# RTC.net
KiCad netlist of a schematic drawn in EAGLE
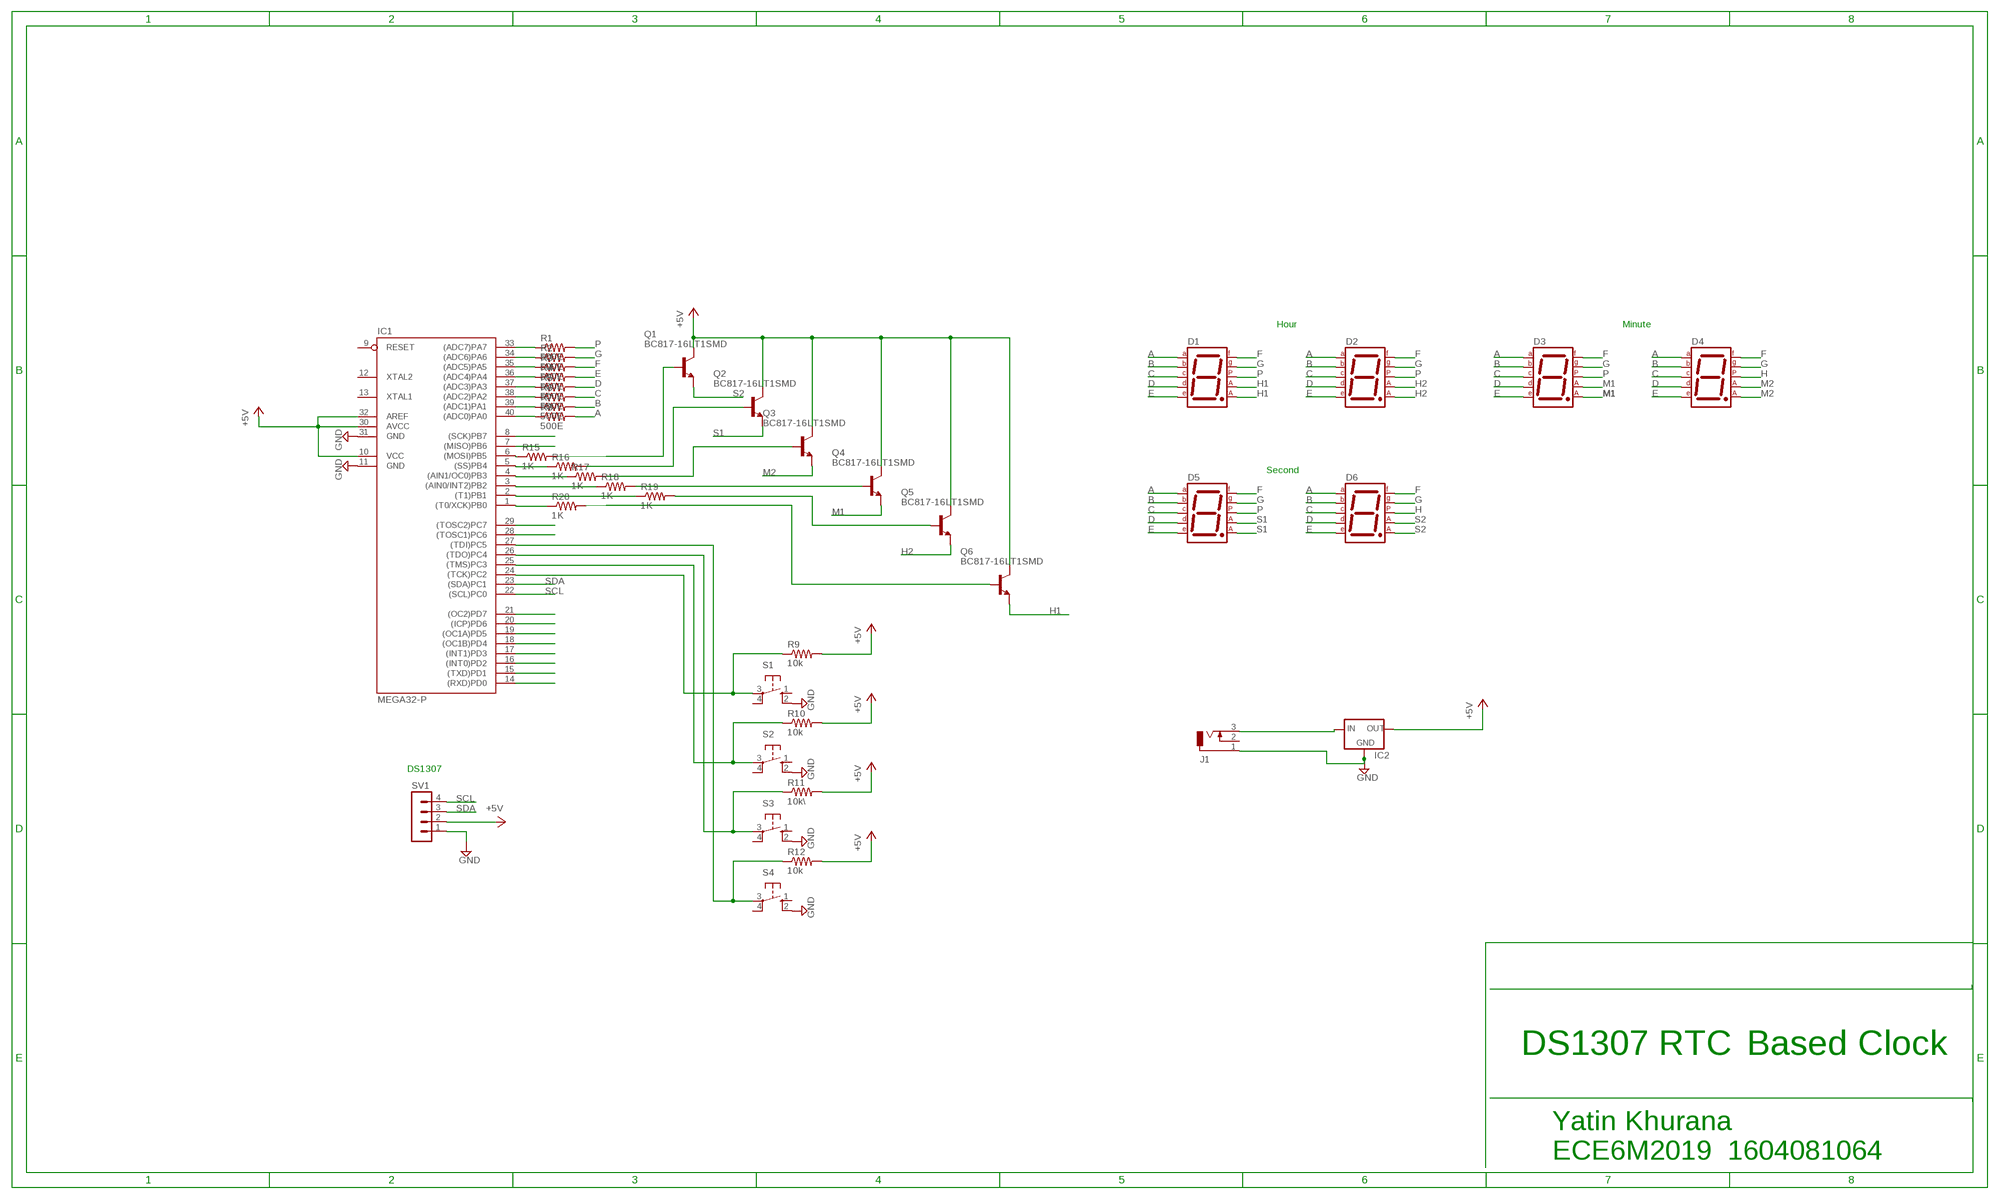
[diagram p0: schematic, sheet 1]

(export (version "E")
  (design (tool "Eeschema 10.0.6"))
  (components
    (comp (ref "D1")
      (value "7SEG-CA")
      (footprint "eagle-import:7SEG-13")
      (libsource (lib "eagle-import") (part "7SEG-CA"))
    )
    (comp (ref "D2")
      (value "7SEG-CA")
      (footprint "eagle-import:7SEG-13")
      (libsource (lib "eagle-import") (part "7SEG-CA"))
    )
    (comp (ref "D3")
      (value "7SEG-CA")
      (footprint "eagle-import:7SEG-13")
      (libsource (lib "eagle-import") (part "7SEG-CA"))
    )
    (comp (ref "D4")
      (value "7SEG-CA")
      (footprint "eagle-import:7SEG-13")
      (libsource (lib "eagle-import") (part "7SEG-CA"))
    )
    (comp (ref "D5")
      (value "7SEG-CA")
      (footprint "eagle-import:7SEG-13")
      (libsource (lib "eagle-import") (part "7SEG-CA"))
    )
    (comp (ref "D6")
      (value "7SEG-CA")
      (footprint "eagle-import:7SEG-13")
      (libsource (lib "eagle-import") (part "7SEG-CA"))
    )
    (comp (ref "IC1")
      (value "MEGA32-P")
      (footprint "eagle-import:DIL40")
      (fields (field (name "MPN") "ATMEGA32-16PU"))
      (libsource (lib "eagle-import") (part "MEGA32-P"))
    )
    (comp (ref "IC2")
      (value "78XXS")
      (footprint "eagle-import:78XXS")
      (libsource (lib "eagle-import") (part "78XXS"))
    )
    (comp (ref "J1")
      (value "DCJ0303")
      (footprint "eagle-import:DCJ0303")
      (libsource (lib "eagle-import") (part "DCJ0303"))
    )
    (comp (ref "Q1")
      (value "BC817-16LT1SMD")
      (footprint "eagle-import:SOT23-BEC")
      (libsource (lib "eagle-import") (part "BC817SMD-16LT1"))
    )
    (comp (ref "Q2")
      (value "BC817-16LT1SMD")
      (footprint "eagle-import:SOT23-BEC")
      (libsource (lib "eagle-import") (part "BC817SMD-16LT1"))
    )
    (comp (ref "Q3")
      (value "BC817-16LT1SMD")
      (footprint "eagle-import:SOT23-BEC")
      (libsource (lib "eagle-import") (part "BC817SMD-16LT1"))
    )
    (comp (ref "Q4")
      (value "BC817-16LT1SMD")
      (footprint "eagle-import:SOT23-BEC")
      (libsource (lib "eagle-import") (part "BC817SMD-16LT1"))
    )
    (comp (ref "Q5")
      (value "BC817-16LT1SMD")
      (footprint "eagle-import:SOT23-BEC")
      (libsource (lib "eagle-import") (part "BC817SMD-16LT1"))
    )
    (comp (ref "Q6")
      (value "BC817-16LT1SMD")
      (footprint "eagle-import:SOT23-BEC")
      (libsource (lib "eagle-import") (part "BC817SMD-16LT1"))
    )
    (comp (ref "R1")
      (value "500E")
      (footprint "eagle-import:M1206")
      (libsource (lib "eagle-import") (part "R-US_M1206"))
    )
    (comp (ref "R2")
      (value "500E")
      (footprint "eagle-import:M1206")
      (libsource (lib "eagle-import") (part "R-US_M1206"))
    )
    (comp (ref "R3")
      (value "500E")
      (footprint "eagle-import:M1206")
      (libsource (lib "eagle-import") (part "R-US_M1206"))
    )
    (comp (ref "R4")
      (value "500E")
      (footprint "eagle-import:M1206")
      (libsource (lib "eagle-import") (part "R-US_M1206"))
    )
    (comp (ref "R5")
      (value "500E")
      (footprint "eagle-import:M1206")
      (libsource (lib "eagle-import") (part "R-US_M1206"))
    )
    (comp (ref "R6")
      (value "500E")
      (footprint "eagle-import:M1206")
      (libsource (lib "eagle-import") (part "R-US_M1206"))
    )
    (comp (ref "R7")
      (value "500E")
      (footprint "eagle-import:M1206")
      (libsource (lib "eagle-import") (part "R-US_M1206"))
    )
    (comp (ref "R8")
      (value "500E")
      (footprint "eagle-import:M1206")
      (libsource (lib "eagle-import") (part "R-US_M1206"))
    )
    (comp (ref "R9")
      (value "10k")
      (footprint "eagle-import:M1206")
      (libsource (lib "eagle-import") (part "R-US_M1206"))
    )
    (comp (ref "R10")
      (value "10k")
      (footprint "eagle-import:M1206")
      (libsource (lib "eagle-import") (part "R-US_M1206"))
    )
    (comp (ref "R11")
      (value "10k\\")
      (footprint "eagle-import:M1206")
      (libsource (lib "eagle-import") (part "R-US_M1206"))
    )
    (comp (ref "R12")
      (value "10k")
      (footprint "eagle-import:M1206")
      (libsource (lib "eagle-import") (part "R-US_M1206"))
    )
    (comp (ref "R15")
      (value "1K")
      (footprint "eagle-import:M1206")
      (libsource (lib "eagle-import") (part "R-US_M1206"))
    )
    (comp (ref "R16")
      (value "1K")
      (footprint "eagle-import:M1206")
      (libsource (lib "eagle-import") (part "R-US_M1206"))
    )
    (comp (ref "R17")
      (value "1K")
      (footprint "eagle-import:M1206")
      (libsource (lib "eagle-import") (part "R-US_M1206"))
    )
    (comp (ref "R18")
      (value "1K")
      (footprint "eagle-import:M1206")
      (libsource (lib "eagle-import") (part "R-US_M1206"))
    )
    (comp (ref "R19")
      (value "1K")
      (footprint "eagle-import:M1206")
      (libsource (lib "eagle-import") (part "R-US_M1206"))
    )
    (comp (ref "R20")
      (value "1K")
      (footprint "eagle-import:M1206")
      (libsource (lib "eagle-import") (part "R-US_M1206"))
    )
    (comp (ref "S1")
      (value "10-XX")
      (footprint "eagle-import:B3F-10XX")
      (fields (field (name "MPN") "B3F-1000"))
      (libsource (lib "eagle-import") (part "10-XX"))
    )
    (comp (ref "S2")
      (value "10-XX")
      (footprint "eagle-import:B3F-10XX")
      (fields (field (name "MPN") "B3F-1000"))
      (libsource (lib "eagle-import") (part "10-XX"))
    )
    (comp (ref "S3")
      (value "10-XX")
      (footprint "eagle-import:B3F-10XX")
      (fields (field (name "MPN") "B3F-1000"))
      (libsource (lib "eagle-import") (part "10-XX"))
    )
    (comp (ref "S4")
      (value "10-XX")
      (footprint "eagle-import:B3F-10XX")
      (fields (field (name "MPN") "B3F-1000"))
      (libsource (lib "eagle-import") (part "10-XX"))
    )
    (comp (ref "SV1")
      (value "MA04-1")
      (footprint "eagle-import:MA04-1")
      (libsource (lib "eagle-import") (part "MA04-1"))
    )
  )
  (nets
    (net (code "1") (name "+5V") (class "Default")
      (node (ref "IC1") (pin "10") (pinfunction "VCC_10") (pintype "power_in"))
      (node (ref "IC1") (pin "30") (pinfunction "AVCC_30") (pintype "power_in"))
      (node (ref "IC1") (pin "32") (pinfunction "AREF_32") (pintype "passive"))
      (node (ref "IC2") (pin "OUT") (pinfunction "OUT_OUT") (pintype "passive"))
      (node (ref "Q1") (pin "C") (pinfunction "C_C") (pintype "passive"))
      (node (ref "Q2") (pin "C") (pinfunction "C_C") (pintype "passive"))
      (node (ref "Q3") (pin "C") (pinfunction "C_C") (pintype "passive"))
      (node (ref "Q4") (pin "C") (pinfunction "C_C") (pintype "passive"))
      (node (ref "Q5") (pin "C") (pinfunction "C_C") (pintype "passive"))
      (node (ref "Q6") (pin "C") (pinfunction "C_C") (pintype "passive"))
      (node (ref "R10") (pin "2") (pinfunction "2_2") (pintype "passive"))
      (node (ref "R11") (pin "2") (pinfunction "2_2") (pintype "passive"))
      (node (ref "R12") (pin "2") (pinfunction "2_2") (pintype "passive"))
      (node (ref "R9") (pin "2") (pinfunction "2_2") (pintype "passive"))
      (node (ref "SV1") (pin "2") (pinfunction "2_2") (pintype "passive"))
    )
    (net (code "2") (name "/A") (class "Default")
      (node (ref "D1") (pin "7") (pinfunction "A_7") (pintype "passive"))
      (node (ref "D2") (pin "7") (pinfunction "A_7") (pintype "passive"))
      (node (ref "D3") (pin "7") (pinfunction "A_7") (pintype "passive"))
      (node (ref "D4") (pin "7") (pinfunction "A_7") (pintype "passive"))
      (node (ref "D5") (pin "7") (pinfunction "A_7") (pintype "passive"))
      (node (ref "D6") (pin "7") (pinfunction "A_7") (pintype "passive"))
      (node (ref "R8") (pin "2") (pinfunction "2_2") (pintype "passive"))
    )
    (net (code "3") (name "/B") (class "Default")
      (node (ref "D1") (pin "6") (pinfunction "B_6") (pintype "passive"))
      (node (ref "D2") (pin "6") (pinfunction "B_6") (pintype "passive"))
      (node (ref "D3") (pin "6") (pinfunction "B_6") (pintype "passive"))
      (node (ref "D4") (pin "6") (pinfunction "B_6") (pintype "passive"))
      (node (ref "D5") (pin "6") (pinfunction "B_6") (pintype "passive"))
      (node (ref "D6") (pin "6") (pinfunction "B_6") (pintype "passive"))
      (node (ref "R7") (pin "2") (pinfunction "2_2") (pintype "passive"))
    )
    (net (code "4") (name "/C") (class "Default")
      (node (ref "D1") (pin "4") (pinfunction "C_4") (pintype "passive"))
      (node (ref "D2") (pin "4") (pinfunction "C_4") (pintype "passive"))
      (node (ref "D3") (pin "4") (pinfunction "C_4") (pintype "passive"))
      (node (ref "D4") (pin "4") (pinfunction "C_4") (pintype "passive"))
      (node (ref "D5") (pin "4") (pinfunction "C_4") (pintype "passive"))
      (node (ref "D6") (pin "4") (pinfunction "C_4") (pintype "passive"))
      (node (ref "R6") (pin "2") (pinfunction "2_2") (pintype "passive"))
    )
    (net (code "5") (name "/D") (class "Default")
      (node (ref "D1") (pin "2") (pinfunction "D_2") (pintype "passive"))
      (node (ref "D2") (pin "2") (pinfunction "D_2") (pintype "passive"))
      (node (ref "D3") (pin "2") (pinfunction "D_2") (pintype "passive"))
      (node (ref "D4") (pin "2") (pinfunction "D_2") (pintype "passive"))
      (node (ref "D5") (pin "2") (pinfunction "D_2") (pintype "passive"))
      (node (ref "D6") (pin "2") (pinfunction "D_2") (pintype "passive"))
      (node (ref "R5") (pin "2") (pinfunction "2_2") (pintype "passive"))
    )
    (net (code "6") (name "/E") (class "Default")
      (node (ref "D1") (pin "1") (pinfunction "E_1") (pintype "passive"))
      (node (ref "D2") (pin "1") (pinfunction "E_1") (pintype "passive"))
      (node (ref "D3") (pin "1") (pinfunction "E_1") (pintype "passive"))
      (node (ref "D4") (pin "1") (pinfunction "E_1") (pintype "passive"))
      (node (ref "D5") (pin "1") (pinfunction "E_1") (pintype "passive"))
      (node (ref "D6") (pin "1") (pinfunction "E_1") (pintype "passive"))
      (node (ref "R4") (pin "2") (pinfunction "2_2") (pintype "passive"))
    )
    (net (code "7") (name "/F") (class "Default")
      (node (ref "D1") (pin "9") (pinfunction "F_9") (pintype "passive"))
      (node (ref "D2") (pin "9") (pinfunction "F_9") (pintype "passive"))
      (node (ref "D3") (pin "9") (pinfunction "F_9") (pintype "passive"))
      (node (ref "D4") (pin "9") (pinfunction "F_9") (pintype "passive"))
      (node (ref "D5") (pin "9") (pinfunction "F_9") (pintype "passive"))
      (node (ref "D6") (pin "9") (pinfunction "F_9") (pintype "passive"))
      (node (ref "R3") (pin "2") (pinfunction "2_2") (pintype "passive"))
    )
    (net (code "8") (name "/G") (class "Default")
      (node (ref "D1") (pin "10") (pinfunction "G_10") (pintype "passive"))
      (node (ref "D2") (pin "10") (pinfunction "G_10") (pintype "passive"))
      (node (ref "D3") (pin "10") (pinfunction "G_10") (pintype "passive"))
      (node (ref "D4") (pin "10") (pinfunction "G_10") (pintype "passive"))
      (node (ref "D5") (pin "10") (pinfunction "G_10") (pintype "passive"))
      (node (ref "D6") (pin "10") (pinfunction "G_10") (pintype "passive"))
      (node (ref "R2") (pin "2") (pinfunction "2_2") (pintype "passive"))
    )
    (net (code "9") (name "/H") (class "Default")
      (node (ref "D4") (pin "5") (pinfunction "DP_5") (pintype "passive"))
      (node (ref "D6") (pin "5") (pinfunction "DP_5") (pintype "passive"))
    )
    (net (code "10") (name "/H1") (class "Default")
      (node (ref "D1") (pin "3") (pinfunction "CA1_3") (pintype "passive"))
      (node (ref "D1") (pin "8") (pinfunction "CA2_8") (pintype "passive"))
      (node (ref "Q6") (pin "E") (pinfunction "E_E") (pintype "passive"))
    )
    (net (code "11") (name "/H2") (class "Default")
      (node (ref "D2") (pin "3") (pinfunction "CA1_3") (pintype "passive"))
      (node (ref "D2") (pin "8") (pinfunction "CA2_8") (pintype "passive"))
      (node (ref "Q5") (pin "E") (pinfunction "E_E") (pintype "passive"))
    )
    (net (code "12") (name "/M1") (class "Default")
      (node (ref "D3") (pin "3") (pinfunction "CA1_3") (pintype "passive"))
      (node (ref "D3") (pin "8") (pinfunction "CA2_8") (pintype "passive"))
      (node (ref "Q4") (pin "E") (pinfunction "E_E") (pintype "passive"))
    )
    (net (code "13") (name "/M2") (class "Default")
      (node (ref "D4") (pin "3") (pinfunction "CA1_3") (pintype "passive"))
      (node (ref "D4") (pin "8") (pinfunction "CA2_8") (pintype "passive"))
      (node (ref "Q3") (pin "E") (pinfunction "E_E") (pintype "passive"))
    )
    (net (code "14") (name "/P") (class "Default")
      (node (ref "D1") (pin "5") (pinfunction "DP_5") (pintype "passive"))
      (node (ref "D2") (pin "5") (pinfunction "DP_5") (pintype "passive"))
      (node (ref "D3") (pin "5") (pinfunction "DP_5") (pintype "passive"))
      (node (ref "D5") (pin "5") (pinfunction "DP_5") (pintype "passive"))
      (node (ref "R1") (pin "2") (pinfunction "2_2") (pintype "passive"))
    )
    (net (code "15") (name "/S1") (class "Default")
      (node (ref "D5") (pin "3") (pinfunction "CA1_3") (pintype "passive"))
      (node (ref "D5") (pin "8") (pinfunction "CA2_8") (pintype "passive"))
      (node (ref "Q2") (pin "E") (pinfunction "E_E") (pintype "passive"))
    )
    (net (code "16") (name "/S2") (class "Default")
      (node (ref "D6") (pin "3") (pinfunction "CA1_3") (pintype "passive"))
      (node (ref "D6") (pin "8") (pinfunction "CA2_8") (pintype "passive"))
      (node (ref "Q1") (pin "E") (pinfunction "E_E") (pintype "passive"))
    )
    (net (code "17") (name "/SCL") (class "Default")
      (node (ref "IC1") (pin "22") (pinfunction "(SCL)PC0_22") (pintype "bidirectional"))
      (node (ref "SV1") (pin "4") (pinfunction "4_4") (pintype "passive"))
    )
    (net (code "18") (name "/SDA") (class "Default")
      (node (ref "IC1") (pin "23") (pinfunction "(SDA)PC1_23") (pintype "bidirectional"))
      (node (ref "SV1") (pin "3") (pinfunction "3_3") (pintype "passive"))
    )
    (net (code "19") (name "GND") (class "Default")
      (node (ref "IC1") (pin "11") (pinfunction "GND_11") (pintype "power_in"))
      (node (ref "IC1") (pin "31") (pinfunction "GND_31") (pintype "power_in"))
      (node (ref "IC2") (pin "GND") (pinfunction "GND_GND") (pintype "input"))
      (node (ref "J1") (pin "1") (pinfunction "1_1") (pintype "passive"))
      (node (ref "S1") (pin "2") (pinfunction "S1_2") (pintype "passive"))
      (node (ref "S2") (pin "2") (pinfunction "S1_2") (pintype "passive"))
      (node (ref "S3") (pin "2") (pinfunction "S1_2") (pintype "passive"))
      (node (ref "S4") (pin "2") (pinfunction "S1_2") (pintype "passive"))
      (node (ref "SV1") (pin "1") (pinfunction "1_1") (pintype "passive"))
    )
    (net (code "20") (name "Net-(IC1-(ADC0)PA0)") (class "Default")
      (node (ref "IC1") (pin "40") (pinfunction "(ADC0)PA0_40") (pintype "bidirectional"))
      (node (ref "R8") (pin "1") (pinfunction "1_1") (pintype "passive"))
    )
    (net (code "21") (name "Net-(IC1-(ADC1)PA1)") (class "Default")
      (node (ref "IC1") (pin "39") (pinfunction "(ADC1)PA1_39") (pintype "bidirectional"))
      (node (ref "R7") (pin "1") (pinfunction "1_1") (pintype "passive"))
    )
    (net (code "22") (name "Net-(IC1-(ADC2)PA2)") (class "Default")
      (node (ref "IC1") (pin "38") (pinfunction "(ADC2)PA2_38") (pintype "bidirectional"))
      (node (ref "R6") (pin "1") (pinfunction "1_1") (pintype "passive"))
    )
    (net (code "23") (name "Net-(IC1-(ADC3)PA3)") (class "Default")
      (node (ref "IC1") (pin "37") (pinfunction "(ADC3)PA3_37") (pintype "bidirectional"))
      (node (ref "R5") (pin "1") (pinfunction "1_1") (pintype "passive"))
    )
    (net (code "24") (name "Net-(IC1-(ADC4)PA4)") (class "Default")
      (node (ref "IC1") (pin "36") (pinfunction "(ADC4)PA4_36") (pintype "bidirectional"))
      (node (ref "R4") (pin "1") (pinfunction "1_1") (pintype "passive"))
    )
    (net (code "25") (name "Net-(IC1-(ADC5)PA5)") (class "Default")
      (node (ref "IC1") (pin "35") (pinfunction "(ADC5)PA5_35") (pintype "bidirectional"))
      (node (ref "R3") (pin "1") (pinfunction "1_1") (pintype "passive"))
    )
    (net (code "26") (name "Net-(IC1-(ADC6)PA6)") (class "Default")
      (node (ref "IC1") (pin "34") (pinfunction "(ADC6)PA6_34") (pintype "bidirectional"))
      (node (ref "R2") (pin "1") (pinfunction "1_1") (pintype "passive"))
    )
    (net (code "27") (name "Net-(IC1-(ADC7)PA7)") (class "Default")
      (node (ref "IC1") (pin "33") (pinfunction "(ADC7)PA7_33") (pintype "bidirectional"))
      (node (ref "R1") (pin "1") (pinfunction "1_1") (pintype "passive"))
    )
    (net (code "28") (name "Net-(IC1-(AIN0{slash}INT2)PB2)") (class "Default")
      (node (ref "IC1") (pin "3") (pinfunction "(AIN0/INT2)PB2_3") (pintype "bidirectional"))
      (node (ref "R18") (pin "1") (pinfunction "1_1") (pintype "passive"))
    )
    (net (code "29") (name "Net-(IC1-(AIN1{slash}OC0)PB3)") (class "Default")
      (node (ref "IC1") (pin "4") (pinfunction "(AIN1/OC0)PB3_4") (pintype "bidirectional"))
      (node (ref "R17") (pin "1") (pinfunction "1_1") (pintype "passive"))
    )
    (net (code "30") (name "Net-(IC1-(MOSI)PB5)") (class "Default")
      (node (ref "IC1") (pin "6") (pinfunction "(MOSI)PB5_6") (pintype "bidirectional"))
      (node (ref "R15") (pin "1") (pinfunction "1_1") (pintype "passive"))
    )
    (net (code "31") (name "Net-(IC1-(SS)PB4)") (class "Default")
      (node (ref "IC1") (pin "5") (pinfunction "(SS)PB4_5") (pintype "bidirectional"))
      (node (ref "R16") (pin "1") (pinfunction "1_1") (pintype "passive"))
    )
    (net (code "32") (name "Net-(IC1-(T0{slash}XCK)PB0)") (class "Default")
      (node (ref "IC1") (pin "1") (pinfunction "(T0/XCK)PB0_1") (pintype "bidirectional"))
      (node (ref "R20") (pin "1") (pinfunction "1_1") (pintype "passive"))
    )
    (net (code "33") (name "Net-(IC1-(T1)PB1)") (class "Default")
      (node (ref "IC1") (pin "2") (pinfunction "(T1)PB1_2") (pintype "bidirectional"))
      (node (ref "R19") (pin "1") (pinfunction "1_1") (pintype "passive"))
    )
    (net (code "34") (name "Net-(IC1-(TCK)PC2)") (class "Default")
      (node (ref "IC1") (pin "24") (pinfunction "(TCK)PC2_24") (pintype "bidirectional"))
      (node (ref "R9") (pin "1") (pinfunction "1_1") (pintype "passive"))
      (node (ref "S1") (pin "3") (pinfunction "P_3") (pintype "passive"))
    )
    (net (code "35") (name "Net-(IC1-(TDI)PC5)") (class "Default")
      (node (ref "IC1") (pin "27") (pinfunction "(TDI)PC5_27") (pintype "bidirectional"))
      (node (ref "R12") (pin "1") (pinfunction "1_1") (pintype "passive"))
      (node (ref "S4") (pin "3") (pinfunction "P_3") (pintype "passive"))
    )
    (net (code "36") (name "Net-(IC1-(TDO)PC4)") (class "Default")
      (node (ref "IC1") (pin "26") (pinfunction "(TDO)PC4_26") (pintype "bidirectional"))
      (node (ref "R11") (pin "1") (pinfunction "1_1") (pintype "passive"))
      (node (ref "S3") (pin "3") (pinfunction "P_3") (pintype "passive"))
    )
    (net (code "37") (name "Net-(IC1-(TMS)PC3)") (class "Default")
      (node (ref "IC1") (pin "25") (pinfunction "(TMS)PC3_25") (pintype "bidirectional"))
      (node (ref "R10") (pin "1") (pinfunction "1_1") (pintype "passive"))
      (node (ref "S2") (pin "3") (pinfunction "P_3") (pintype "passive"))
    )
    (net (code "38") (name "Net-(IC2-PadIN)") (class "Default")
      (node (ref "IC2") (pin "IN") (pinfunction "IN_IN") (pintype "input"))
      (node (ref "J1") (pin "3") (pinfunction "3_3") (pintype "passive"))
    )
    (net (code "39") (name "Net-(Q1-PadB)") (class "Default")
      (node (ref "Q1") (pin "B") (pinfunction "B_B") (pintype "passive"))
      (node (ref "R15") (pin "2") (pinfunction "2_2") (pintype "passive"))
    )
    (net (code "40") (name "Net-(Q2-PadB)") (class "Default")
      (node (ref "Q2") (pin "B") (pinfunction "B_B") (pintype "passive"))
      (node (ref "R16") (pin "2") (pinfunction "2_2") (pintype "passive"))
    )
    (net (code "41") (name "Net-(Q3-PadB)") (class "Default")
      (node (ref "Q3") (pin "B") (pinfunction "B_B") (pintype "passive"))
      (node (ref "R17") (pin "2") (pinfunction "2_2") (pintype "passive"))
    )
    (net (code "42") (name "Net-(Q4-PadB)") (class "Default")
      (node (ref "Q4") (pin "B") (pinfunction "B_B") (pintype "passive"))
      (node (ref "R18") (pin "2") (pinfunction "2_2") (pintype "passive"))
    )
    (net (code "43") (name "Net-(Q5-PadB)") (class "Default")
      (node (ref "Q5") (pin "B") (pinfunction "B_B") (pintype "passive"))
      (node (ref "R19") (pin "2") (pinfunction "2_2") (pintype "passive"))
    )
    (net (code "44") (name "Net-(Q6-PadB)") (class "Default")
      (node (ref "Q6") (pin "B") (pinfunction "B_B") (pintype "passive"))
      (node (ref "R20") (pin "2") (pinfunction "2_2") (pintype "passive"))
    )
    (net (code "45") (name "unconnected-(IC1-(ICP)PD6-Pad20)") (class "Default")
      (node (ref "IC1") (pin "20") (pinfunction "(ICP)PD6_20") (pintype "bidirectional"))
    )
    (net (code "46") (name "unconnected-(IC1-(INT0)PD2-Pad16)") (class "Default")
      (node (ref "IC1") (pin "16") (pinfunction "(INT0)PD2_16") (pintype "bidirectional"))
    )
    (net (code "47") (name "unconnected-(IC1-(INT1)PD3-Pad17)") (class "Default")
      (node (ref "IC1") (pin "17") (pinfunction "(INT1)PD3_17") (pintype "bidirectional"))
    )
    (net (code "48") (name "unconnected-(IC1-(MISO)PB6-Pad7)") (class "Default")
      (node (ref "IC1") (pin "7") (pinfunction "(MISO)PB6_7") (pintype "bidirectional"))
    )
    (net (code "49") (name "unconnected-(IC1-(OC1A)PD5-Pad19)") (class "Default")
      (node (ref "IC1") (pin "19") (pinfunction "(OC1A)PD5_19") (pintype "bidirectional"))
    )
    (net (code "50") (name "unconnected-(IC1-(OC1B)PD4-Pad18)") (class "Default")
      (node (ref "IC1") (pin "18") (pinfunction "(OC1B)PD4_18") (pintype "bidirectional"))
    )
    (net (code "51") (name "unconnected-(IC1-(OC2)PD7-Pad21)") (class "Default")
      (node (ref "IC1") (pin "21") (pinfunction "(OC2)PD7_21") (pintype "bidirectional"))
    )
    (net (code "52") (name "unconnected-(IC1-(RXD)PD0-Pad14)") (class "Default")
      (node (ref "IC1") (pin "14") (pinfunction "(RXD)PD0_14") (pintype "bidirectional"))
    )
    (net (code "53") (name "unconnected-(IC1-(SCK)PB7-Pad8)") (class "Default")
      (node (ref "IC1") (pin "8") (pinfunction "(SCK)PB7_8") (pintype "bidirectional"))
    )
    (net (code "54") (name "unconnected-(IC1-(TOSC1)PC6-Pad28)") (class "Default")
      (node (ref "IC1") (pin "28") (pinfunction "(TOSC1)PC6_28") (pintype "bidirectional"))
    )
    (net (code "55") (name "unconnected-(IC1-(TOSC2)PC7-Pad29)") (class "Default")
      (node (ref "IC1") (pin "29") (pinfunction "(TOSC2)PC7_29") (pintype "bidirectional"))
    )
    (net (code "56") (name "unconnected-(IC1-(TXD)PD1-Pad15)") (class "Default")
      (node (ref "IC1") (pin "15") (pinfunction "(TXD)PD1_15") (pintype "bidirectional"))
    )
    (net (code "57") (name "unconnected-(IC1-RESET-Pad9)") (class "Default")
      (node (ref "IC1") (pin "9") (pinfunction "RESET_9") (pintype "input"))
    )
    (net (code "58") (name "unconnected-(IC1-XTAL1-Pad13)") (class "Default")
      (node (ref "IC1") (pin "13") (pinfunction "XTAL1_13") (pintype "bidirectional"))
    )
    (net (code "59") (name "unconnected-(IC1-XTAL2-Pad12)") (class "Default")
      (node (ref "IC1") (pin "12") (pinfunction "XTAL2_12") (pintype "bidirectional"))
    )
    (net (code "60") (name "unconnected-(J1-Pad2)") (class "Default")
      (node (ref "J1") (pin "2") (pinfunction "2_2") (pintype "passive"))
    )
    (net (code "61") (name "unconnected-(S1-P1-Pad4)") (class "Default")
      (node (ref "S1") (pin "4") (pinfunction "P1_4") (pintype "passive"))
    )
    (net (code "62") (name "unconnected-(S1-S-Pad1)") (class "Default")
      (node (ref "S1") (pin "1") (pinfunction "S_1") (pintype "passive"))
    )
    (net (code "63") (name "unconnected-(S2-P1-Pad4)") (class "Default")
      (node (ref "S2") (pin "4") (pinfunction "P1_4") (pintype "passive"))
    )
    (net (code "64") (name "unconnected-(S2-S-Pad1)") (class "Default")
      (node (ref "S2") (pin "1") (pinfunction "S_1") (pintype "passive"))
    )
    (net (code "65") (name "unconnected-(S3-P1-Pad4)") (class "Default")
      (node (ref "S3") (pin "4") (pinfunction "P1_4") (pintype "passive"))
    )
    (net (code "66") (name "unconnected-(S3-S-Pad1)") (class "Default")
      (node (ref "S3") (pin "1") (pinfunction "S_1") (pintype "passive"))
    )
    (net (code "67") (name "unconnected-(S4-P1-Pad4)") (class "Default")
      (node (ref "S4") (pin "4") (pinfunction "P1_4") (pintype "passive"))
    )
    (net (code "68") (name "unconnected-(S4-S-Pad1)") (class "Default")
      (node (ref "S4") (pin "1") (pinfunction "S_1") (pintype "passive"))
    )
  )
)
